# Sensors.net
KiCad netlist of a schematic drawn in Altium Designer
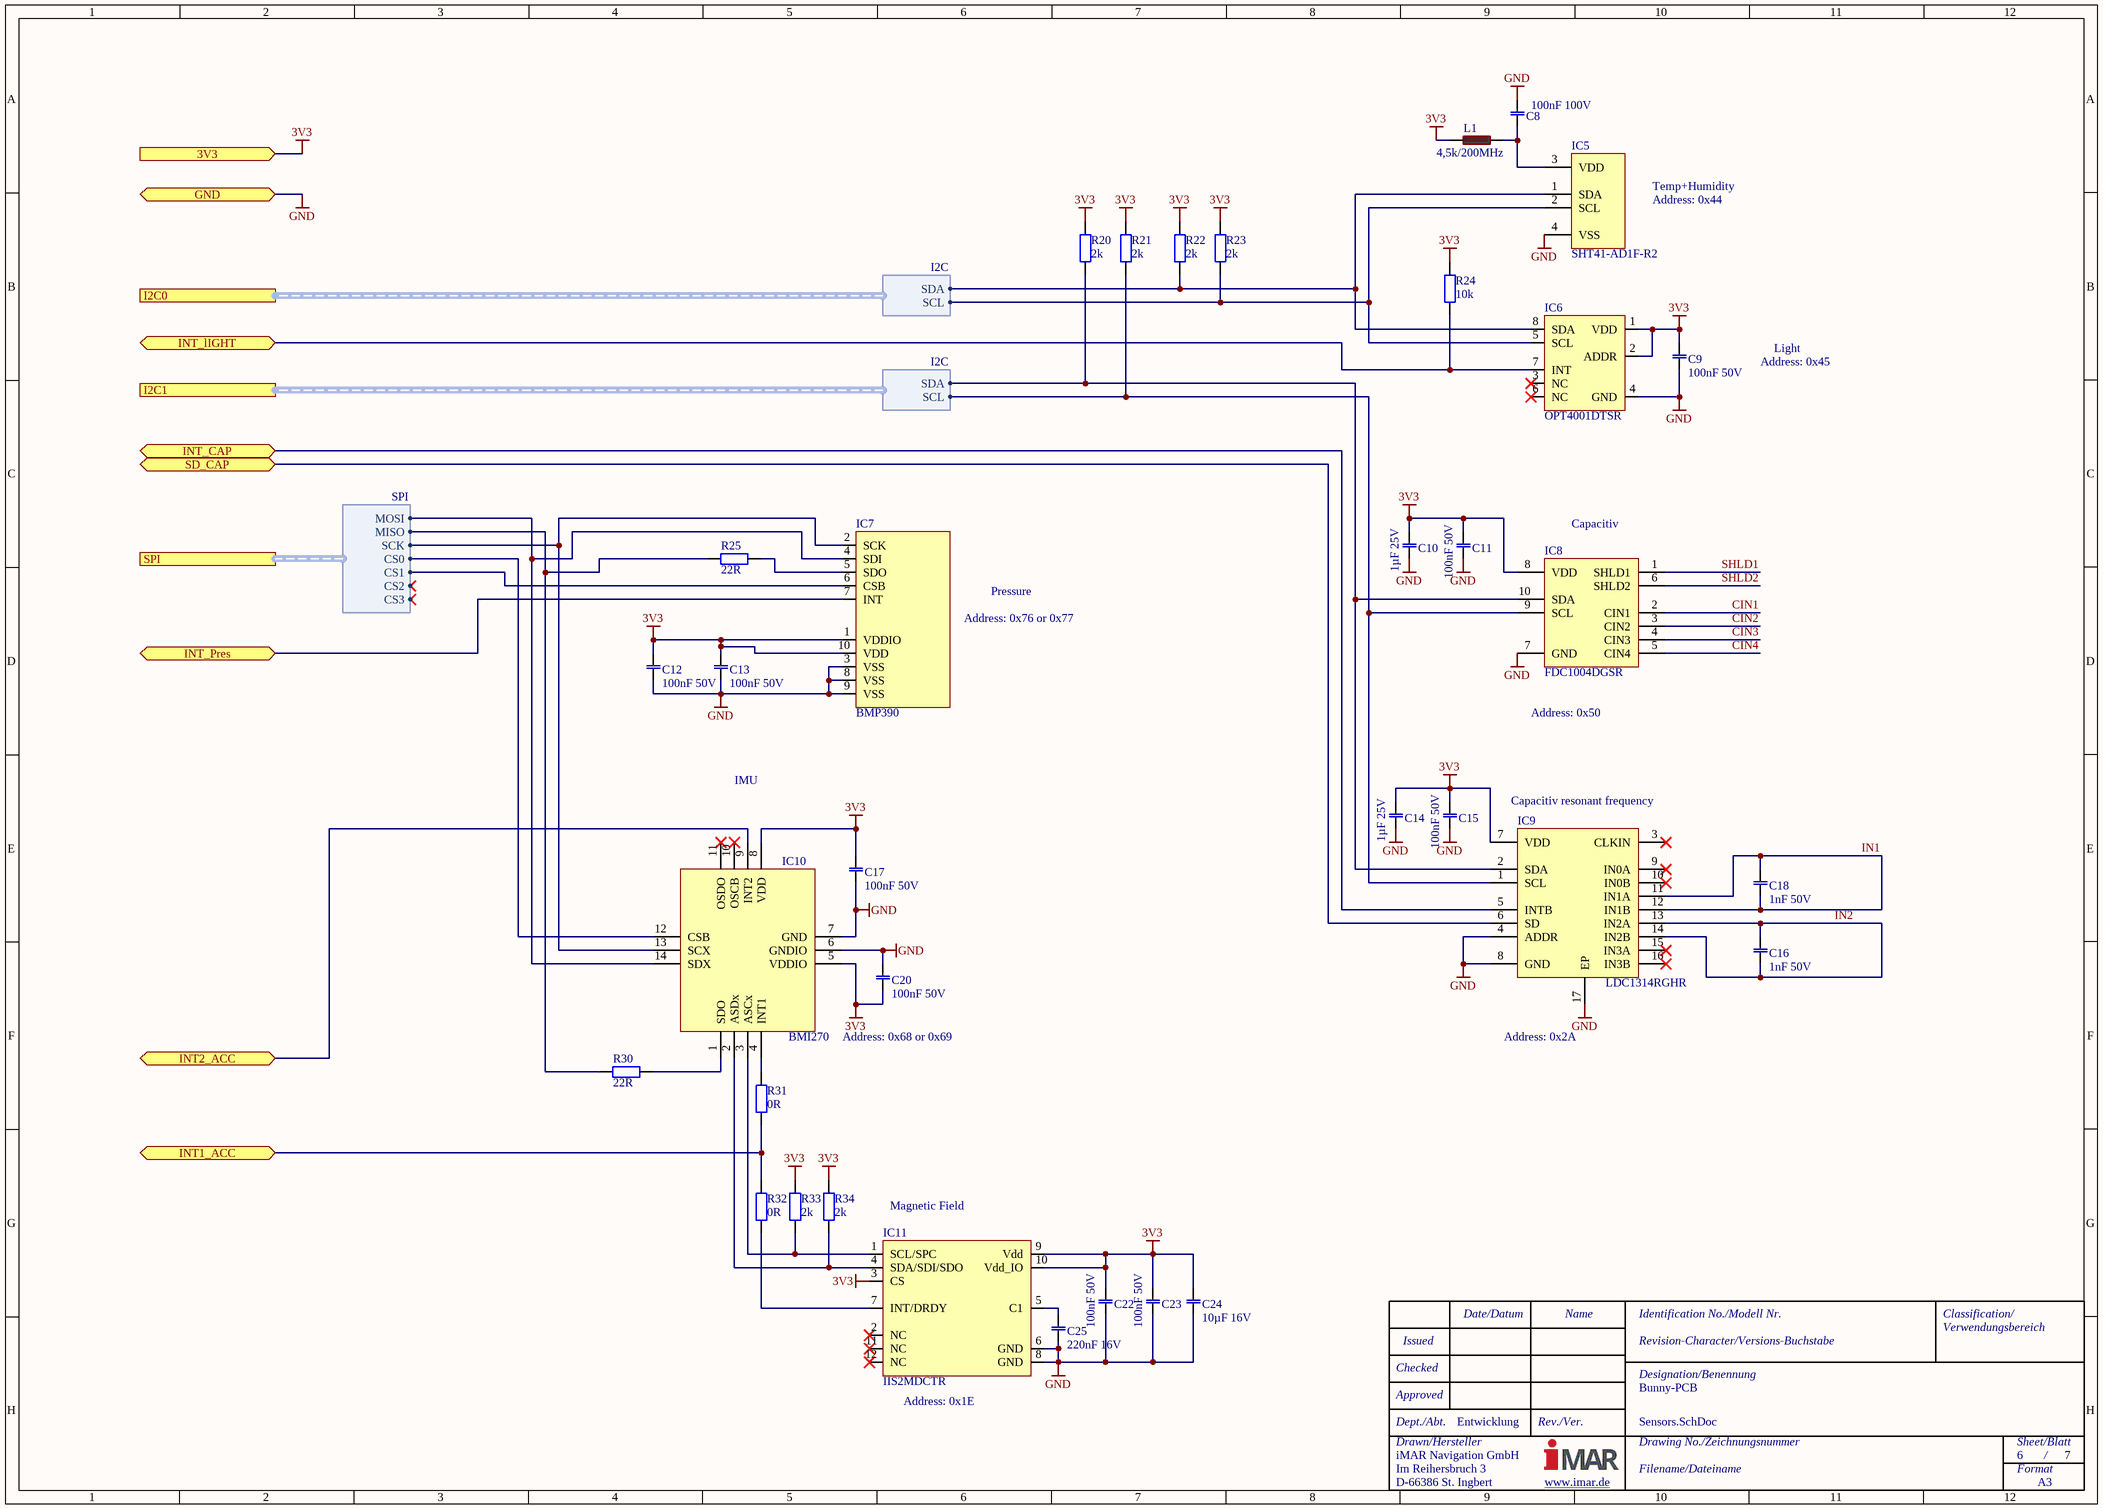
[diagram p0: Sensors.SchDoc]

(export (version "E")
  (design (tool "Eeschema 10.0.6"))
  (components
    (comp (ref "C8")
      (value "100nF 100V")
      (footprint "CAPC1608L")
      (description "100nF  100V  Ceramic  0603  10%  X7R")
      (fields (field (name "VOLTAGE") "100V") (field (name "MANUFACTURER") "unspecified"))
      (libsource (lib "iMAR Workspace") (part "Kondensator"))
    )
    (comp (ref "C9")
      (value "100nF 50V")
      (footprint "CAPC1005N")
      (description "100nF  50V  Ceramic  0402  10%  X7R")
      (fields (field (name "VOLTAGE") "50V") (field (name "MANUFACTURER") "unspecified"))
      (libsource (lib "iMAR Workspace") (part "Kondensator"))
    )
    (comp (ref "C10")
      (value "1µF 25V")
      (footprint "CAPC1005N")
      (description "1µF  25V  Ceramic  0402  10%  X5R")
      (fields (field (name "VOLTAGE") "25V") (field (name "MANUFACTURER") "unspecified"))
      (libsource (lib "iMAR Workspace") (part "Kondensator"))
    )
    (comp (ref "C11")
      (value "100nF 50V")
      (footprint "CAPC1005N")
      (description "100nF  50V  Ceramic  0402  10%  X7R")
      (fields (field (name "VOLTAGE") "50V") (field (name "MANUFACTURER") "unspecified"))
      (libsource (lib "iMAR Workspace") (part "Kondensator"))
    )
    (comp (ref "C12")
      (value "100nF 50V")
      (footprint "CAPC1005N")
      (description "100nF  50V  Ceramic  0402  10%  X7R")
      (fields (field (name "VOLTAGE") "50V") (field (name "MANUFACTURER") "unspecified"))
      (libsource (lib "iMAR Workspace") (part "Kondensator"))
    )
    (comp (ref "C13")
      (value "100nF 50V")
      (footprint "CAPC1005N")
      (description "100nF  50V  Ceramic  0402  10%  X7R")
      (fields (field (name "VOLTAGE") "50V") (field (name "MANUFACTURER") "unspecified"))
      (libsource (lib "iMAR Workspace") (part "Kondensator"))
    )
    (comp (ref "C14")
      (value "1µF 25V")
      (footprint "CAPC1005N")
      (description "1µF  25V  Ceramic  0402  10%  X5R")
      (fields (field (name "VOLTAGE") "25V") (field (name "MANUFACTURER") "unspecified"))
      (libsource (lib "iMAR Workspace") (part "Kondensator"))
    )
    (comp (ref "C15")
      (value "100nF 50V")
      (footprint "CAPC1005N")
      (description "100nF  50V  Ceramic  0402  10%  X7R")
      (fields (field (name "VOLTAGE") "50V") (field (name "MANUFACTURER") "unspecified"))
      (libsource (lib "iMAR Workspace") (part "Kondensator"))
    )
    (comp (ref "C16")
      (value "1nF 50V")
      (footprint "CAPC1608L")
      (description "1nF 50V Ceramic 0603 1% C0G(NP0)")
      (fields (field (name "TOLERANCE") "1%") (field (name "MANUFACTURER") "VISHAY"))
      (libsource (lib "iMAR Workspace") (part "Kondensator"))
    )
    (comp (ref "C17")
      (value "100nF 50V")
      (footprint "CAPC1005N")
      (description "100nF  50V  Ceramic  0402  10%  X7R")
      (fields (field (name "VOLTAGE") "50V") (field (name "MANUFACTURER") "unspecified"))
      (libsource (lib "iMAR Workspace") (part "Kondensator"))
    )
    (comp (ref "C18")
      (value "1nF 50V")
      (footprint "CAPC1608L")
      (description "1nF 50V Ceramic 0603 1% C0G(NP0)")
      (fields (field (name "TOLERANCE") "1%") (field (name "MANUFACTURER") "VISHAY"))
      (libsource (lib "iMAR Workspace") (part "Kondensator"))
    )
    (comp (ref "C20")
      (value "100nF 50V")
      (footprint "CAPC1005N")
      (description "100nF  50V  Ceramic  0402  10%  X7R")
      (fields (field (name "VOLTAGE") "50V") (field (name "MANUFACTURER") "unspecified"))
      (libsource (lib "iMAR Workspace") (part "Kondensator"))
    )
    (comp (ref "C22")
      (value "100nF 50V")
      (footprint "CAPC1005N")
      (description "100nF  50V  Ceramic  0402  10%  X7R")
      (fields (field (name "VOLTAGE") "50V") (field (name "MANUFACTURER") "unspecified"))
      (libsource (lib "iMAR Workspace") (part "Kondensator"))
    )
    (comp (ref "C23")
      (value "100nF 50V")
      (footprint "CAPC1005N")
      (description "100nF  50V  Ceramic  0402  10%  X7R")
      (fields (field (name "VOLTAGE") "50V") (field (name "MANUFACTURER") "unspecified"))
      (libsource (lib "iMAR Workspace") (part "Kondensator"))
    )
    (comp (ref "C24")
      (value "10µF 16V")
      (footprint "CAPC1608L")
      (description "10µF  16V  Ceramic  0603  10%  X5R")
      (fields (field (name "TOLERANCE") "10%") (field (name "MANUFACTURER") "unspecified"))
      (libsource (lib "iMAR Workspace") (part "Kondensator"))
    )
    (comp (ref "C25")
      (value "220nF 16V")
      (footprint "CAPC1005N")
      (description "220nF  16V  Ceramic  0402  10%  X7R")
      (fields (field (name "MANUFACTURER") "unspecified") (field (name "VOLTAGE") "16V"))
      (libsource (lib "iMAR Workspace") (part "Kondensator"))
    )
    (comp (ref "IC5")
      (value "SHT41-AD1F-R2")
      (footprint "SENSIRION_SHT4x")
      (description "Digital humidity and temperature sensor, ±1.8% / max. ±3.5% RH")
      (fields (field (name "MANUFACTURER") "SENSIRION"))
      (libsource (lib "iMAR Workspace") (part "SHT4x"))
    )
    (comp (ref "IC6")
      (value "OPT4001DTSR")
      (footprint "SOT50P160X60-8N")
      (description "High-speed high-precision digital ambient light sensor (ALS)")
      (fields (field (name "MANUFACTURER") "TEXAS INSTRUMENTS"))
      (libsource (lib "iMAR Workspace") (part "OPT4001DTSR"))
    )
    (comp (ref "IC7")
      (value "BMP390")
      (footprint "BMP390")
      (description "Pressure Sensor")
      (fields (field (name "MANUFACTURER") "BOSCH"))
      (libsource (lib "iMAR Workspace") (part "BMP390"))
    )
    (comp (ref "IC8")
      (value "FDC1004DGSR")
      (footprint "TSSOP50P490X110-10N")
      (description "4-Channel Capacitance-to-Digital Converter for Capacitive Sensing Applications")
      (fields (field (name "MANUFACTURER") "TEXAS INSTRUMENTS"))
      (libsource (lib "iMAR Workspace") (part "FDC1004"))
    )
    (comp (ref "IC9")
      (value "LDC1314RGHR")
      (footprint "QFN65P400X400X80_HS-17N")
      (description "Data Acquisition ADCs/DACs - Specialised 12-bit Inductance- t o-Digital Converter")
      (fields (field (name "MANUFACTURER") "TEXAS INSTRUMENTS"))
      (libsource (lib "iMAR Workspace") (part "LDC1314"))
    )
    (comp (ref "IC10")
      (value "BMI270")
      (footprint "BOSCH_LGA14_BMI_vergroesserte_Pads")
      (description "6-axis, smart, low-power Inertial Measurement Unit")
      (fields (field (name "MANUFACTURER") "BOSCH"))
      (libsource (lib "iMAR Workspace") (part "BMI270"))
    )
    (comp (ref "IC11")
      (value "IIS2MDCTR")
      (footprint "ST_IIS2MDCTR_LGA12C50P4X4_200X200X70")
      (description "High accuracy, ultra-low-power ,3-axis digital output magnetometer")
      (fields (field (name "MANUFACTURER") "ST Microelectronics"))
      (libsource (lib "iMAR Workspace") (part "IIS2MDCTR"))
    )
    (comp (ref "L1")
      (value "4,5k/200MHz")
      (footprint "IND_WE_CBF_0603_Wide_Band")
      (description "4,5k/200MHz  500mA  0603  WE-CBF SMD EMI Suppression Ferrite Bead")
      (fields (field (name "MANUFACTURER") "WUERTH ELEKTRONIK"))
      (libsource (lib "iMAR Workspace") (part "Ferrit-Perle"))
    )
    (comp (ref "R20")
      (value "2k")
      (footprint "RESC1005L")
      (description "2k  0402  62mW  1%  100ppm  50V")
      (fields (field (name "POWER") "62mW") (field (name "TOLERANCE") "1%"))
      (libsource (lib "iMAR Workspace") (part "Widerstand"))
    )
    (comp (ref "R21")
      (value "2k")
      (footprint "RESC1005L")
      (description "2k  0402  62mW  1%  100ppm  50V")
      (fields (field (name "POWER") "62mW") (field (name "TOLERANCE") "1%"))
      (libsource (lib "iMAR Workspace") (part "Widerstand"))
    )
    (comp (ref "R22")
      (value "2k")
      (footprint "RESC1005L")
      (description "2k  0402  62mW  1%  100ppm  50V")
      (fields (field (name "POWER") "62mW") (field (name "TOLERANCE") "1%"))
      (libsource (lib "iMAR Workspace") (part "Widerstand"))
    )
    (comp (ref "R23")
      (value "2k")
      (footprint "RESC1005L")
      (description "2k  0402  62mW  1%  100ppm  50V")
      (fields (field (name "POWER") "62mW") (field (name "TOLERANCE") "1%"))
      (libsource (lib "iMAR Workspace") (part "Widerstand"))
    )
    (comp (ref "R24")
      (value "10k")
      (footprint "RESC1005L")
      (description "10k  0402  62mW  1%  100ppm  50V")
      (fields (field (name "MANUFACTURER") "unspecified") (field (name "POWER") "62mW"))
      (libsource (lib "iMAR Workspace") (part "Widerstand"))
    )
    (comp (ref "R25")
      (value "22R")
      (footprint "RESC1005L")
      (description "22R  0402  62mW  1%  100ppm  50V")
      (fields (field (name "MANUFACTURER") "unspecified") (field (name "POWER") "62mW"))
      (libsource (lib "") (part "Widerstand_1"))
    )
    (comp (ref "R30")
      (value "22R")
      (footprint "RESC1005L")
      (description "22R  0402  62mW  1%  100ppm  50V")
      (fields (field (name "MANUFACTURER") "unspecified") (field (name "POWER") "62mW"))
      (libsource (lib "") (part "Widerstand_1"))
    )
    (comp (ref "R31")
      (value "0R")
      (footprint "RESC1005L")
      (description "0R  0402  0mW  0%  0ppm  0V")
      (fields (field (name "VOLTAGE") "0V") (field (name "TOLERANCE") "0%"))
      (libsource (lib "iMAR Workspace") (part "Widerstand"))
    )
    (comp (ref "R32")
      (value "0R")
      (footprint "RESC1005L")
      (description "0R  0402  0mW  0%  0ppm  0V")
      (fields (field (name "VOLTAGE") "0V") (field (name "TOLERANCE") "0%"))
      (libsource (lib "iMAR Workspace") (part "Widerstand"))
    )
    (comp (ref "R33")
      (value "2k")
      (footprint "RESC1005L")
      (description "2k  0402  62mW  1%  100ppm  50V")
      (fields (field (name "POWER") "62mW") (field (name "TOLERANCE") "1%"))
      (libsource (lib "iMAR Workspace") (part "Widerstand"))
    )
    (comp (ref "R34")
      (value "2k")
      (footprint "RESC1005L")
      (description "2k  0402  62mW  1%  100ppm  50V")
      (fields (field (name "POWER") "62mW") (field (name "TOLERANCE") "1%"))
      (libsource (lib "iMAR Workspace") (part "Widerstand"))
    )
  )
  (nets
    (net (code "3") (name "/CIN1") (class "Default")
      (node (ref "IC8") (pin "2") (pinfunction "CIN1_2") (pintype "passive"))
    )
    (net (code "4") (name "/CIN2") (class "Default")
      (node (ref "IC8") (pin "3") (pinfunction "CIN2_3") (pintype "passive"))
    )
    (net (code "5") (name "/CIN3") (class "Default")
      (node (ref "IC8") (pin "4") (pinfunction "CIN3_4") (pintype "passive"))
    )
    (net (code "6") (name "/CIN4") (class "Default")
      (node (ref "IC8") (pin "5") (pinfunction "CIN4_5") (pintype "passive"))
    )
    (net (code "7") (name "/CS0") (class "Default")
      (node (ref "IC10") (pin "12") (pinfunction "CSB_12") (pintype "passive"))
    )
    (net (code "8") (name "/CS1") (class "Default")
      (node (ref "IC7") (pin "6") (pinfunction "CSB_6") (pintype "passive"))
    )
    (net (code "9") (name "/IN1") (class "Default")
      (node (ref "C18") (pin "1") (pinfunction "1_1") (pintype "passive"))
      (node (ref "C18") (pin "2") (pinfunction "2_2") (pintype "passive"))
      (node (ref "IC9") (pin "11") (pinfunction "IN1A_11") (pintype "passive"))
      (node (ref "IC9") (pin "12") (pinfunction "IN1B_12") (pintype "passive"))
    )
    (net (code "10") (name "/IN2") (class "Default")
      (node (ref "C16") (pin "1") (pinfunction "1_1") (pintype "passive"))
      (node (ref "C16") (pin "2") (pinfunction "2_2") (pintype "passive"))
      (node (ref "IC9") (pin "13") (pinfunction "IN2A_13") (pintype "passive"))
      (node (ref "IC9") (pin "14") (pinfunction "IN2B_14") (pintype "passive"))
    )
    (net (code "11") (name "/INT1_ACC") (class "Default")
      (node (ref "R31") (pin "1") (pinfunction "1_1") (pintype "passive"))
      (node (ref "R32") (pin "2") (pinfunction "2_2") (pintype "passive"))
    )
    (net (code "12") (name "/INT2_ACC") (class "Default")
      (node (ref "IC10") (pin "9") (pinfunction "INT2_9") (pintype "passive"))
    )
    (net (code "13") (name "/INT_CAP") (class "Default")
      (node (ref "IC9") (pin "5") (pinfunction "INTB_5") (pintype "passive"))
    )
    (net (code "14") (name "/INT_Pres") (class "Default")
      (node (ref "IC7") (pin "7") (pinfunction "INT_7") (pintype "passive"))
    )
    (net (code "15") (name "/INT_lIGHT") (class "Default")
      (node (ref "IC6") (pin "7") (pinfunction "INT_7") (pintype "passive"))
      (node (ref "R24") (pin "1") (pinfunction "1_1") (pintype "passive"))
    )
    (net (code "16") (name "/MISO") (class "Default")
      (node (ref "R25") (pin "1") (pinfunction "1_1") (pintype "passive"))
      (node (ref "R30") (pin "1") (pinfunction "1_1") (pintype "passive"))
    )
    (net (code "17") (name "/MOSI") (class "Default")
      (node (ref "IC10") (pin "14") (pinfunction "SDX_14") (pintype "passive"))
      (node (ref "IC7") (pin "4") (pinfunction "SDI_4") (pintype "passive"))
    )
    (net (code "18") (name "/SCK") (class "Default")
      (node (ref "IC10") (pin "13") (pinfunction "SCX_13") (pintype "passive"))
      (node (ref "IC7") (pin "2") (pinfunction "SCK_2") (pintype "passive"))
    )
    (net (code "19") (name "/SD_CAP") (class "Default")
      (node (ref "IC9") (pin "6") (pinfunction "SD_6") (pintype "passive"))
    )
    (net (code "20") (name "/SHLD1") (class "Default")
      (node (ref "IC8") (pin "1") (pinfunction "SHLD1_1") (pintype "passive"))
    )
    (net (code "21") (name "/SHLD2") (class "Default")
      (node (ref "IC8") (pin "6") (pinfunction "SHLD2_6") (pintype "passive"))
    )
    (net (code "24") (name "3V3") (class "Default")
      (node (ref "C10") (pin "2") (pinfunction "2_2") (pintype "passive"))
      (node (ref "C11") (pin "2") (pinfunction "2_2") (pintype "passive"))
      (node (ref "C12") (pin "2") (pinfunction "2_2") (pintype "passive"))
      (node (ref "C13") (pin "2") (pinfunction "2_2") (pintype "passive"))
      (node (ref "C14") (pin "2") (pinfunction "2_2") (pintype "passive"))
      (node (ref "C15") (pin "2") (pinfunction "2_2") (pintype "passive"))
      (node (ref "C17") (pin "2") (pinfunction "2_2") (pintype "passive"))
      (node (ref "C20") (pin "1") (pinfunction "1_1") (pintype "passive"))
      (node (ref "C22") (pin "2") (pinfunction "2_2") (pintype "passive"))
      (node (ref "C23") (pin "2") (pinfunction "2_2") (pintype "passive"))
      (node (ref "C24") (pin "2") (pinfunction "2_2") (pintype "passive"))
      (node (ref "C9") (pin "2") (pinfunction "2_2") (pintype "passive"))
      (node (ref "IC10") (pin "5") (pinfunction "VDDIO_5") (pintype "passive"))
      (node (ref "IC10") (pin "8") (pinfunction "VDD_8") (pintype "passive"))
      (node (ref "IC11") (pin "10") (pinfunction "Vdd_IO_10") (pintype "passive"))
      (node (ref "IC11") (pin "3") (pinfunction "CS_3") (pintype "passive"))
      (node (ref "IC11") (pin "9") (pinfunction "Vdd_9") (pintype "passive"))
      (node (ref "IC6") (pin "1") (pinfunction "VDD_1") (pintype "passive"))
      (node (ref "IC6") (pin "2") (pinfunction "ADDR_2") (pintype "passive"))
      (node (ref "IC7") (pin "1") (pinfunction "VDDIO_1") (pintype "passive"))
      (node (ref "IC7") (pin "10") (pinfunction "VDD_10") (pintype "passive"))
      (node (ref "IC8") (pin "8") (pinfunction "VDD_8") (pintype "passive"))
      (node (ref "IC9") (pin "7") (pinfunction "VDD_7") (pintype "passive"))
      (node (ref "L1") (pin "1") (pinfunction "1_1") (pintype "passive"))
      (node (ref "R20") (pin "2") (pinfunction "2_2") (pintype "passive"))
      (node (ref "R21") (pin "2") (pinfunction "2_2") (pintype "passive"))
      (node (ref "R22") (pin "2") (pinfunction "2_2") (pintype "passive"))
      (node (ref "R23") (pin "2") (pinfunction "2_2") (pintype "passive"))
      (node (ref "R24") (pin "2") (pinfunction "2_2") (pintype "passive"))
      (node (ref "R33") (pin "2") (pinfunction "2_2") (pintype "passive"))
      (node (ref "R34") (pin "2") (pinfunction "2_2") (pintype "passive"))
    )
    (net (code "25") (name "GND") (class "Default")
      (node (ref "C10") (pin "1") (pinfunction "1_1") (pintype "passive"))
      (node (ref "C11") (pin "1") (pinfunction "1_1") (pintype "passive"))
      (node (ref "C12") (pin "1") (pinfunction "1_1") (pintype "passive"))
      (node (ref "C13") (pin "1") (pinfunction "1_1") (pintype "passive"))
      (node (ref "C14") (pin "1") (pinfunction "1_1") (pintype "passive"))
      (node (ref "C15") (pin "1") (pinfunction "1_1") (pintype "passive"))
      (node (ref "C17") (pin "1") (pinfunction "1_1") (pintype "passive"))
      (node (ref "C20") (pin "2") (pinfunction "2_2") (pintype "passive"))
      (node (ref "C22") (pin "1") (pinfunction "1_1") (pintype "passive"))
      (node (ref "C23") (pin "1") (pinfunction "1_1") (pintype "passive"))
      (node (ref "C24") (pin "1") (pinfunction "1_1") (pintype "passive"))
      (node (ref "C25") (pin "2") (pinfunction "2_2") (pintype "passive"))
      (node (ref "C8") (pin "1") (pinfunction "1_1") (pintype "passive"))
      (node (ref "C9") (pin "1") (pinfunction "1_1") (pintype "passive"))
      (node (ref "IC10") (pin "6") (pinfunction "GNDIO_6") (pintype "passive"))
      (node (ref "IC10") (pin "7") (pinfunction "GND_7") (pintype "passive"))
      (node (ref "IC11") (pin "6") (pinfunction "GND_6") (pintype "passive"))
      (node (ref "IC11") (pin "8") (pinfunction "GND_8") (pintype "passive"))
      (node (ref "IC5") (pin "4") (pinfunction "VSS_4") (pintype "passive"))
      (node (ref "IC6") (pin "4") (pinfunction "GND_4") (pintype "passive"))
      (node (ref "IC7") (pin "3") (pinfunction "VSS_3") (pintype "passive"))
      (node (ref "IC7") (pin "8") (pinfunction "VSS_8") (pintype "passive"))
      (node (ref "IC7") (pin "9") (pinfunction "VSS_9") (pintype "passive"))
      (node (ref "IC8") (pin "7") (pinfunction "GND_7") (pintype "passive"))
      (node (ref "IC9") (pin "17") (pinfunction "EP_17") (pintype "passive"))
      (node (ref "IC9") (pin "4") (pinfunction "ADDR_4") (pintype "passive"))
      (node (ref "IC9") (pin "8") (pinfunction "GND_8") (pintype "passive"))
    )
    (net (code "26") (name "Net-(IC5-SCL)") (class "Default")
      (node (ref "IC5") (pin "2") (pinfunction "SCL_2") (pintype "passive"))
      (node (ref "IC6") (pin "5") (pinfunction "SCL_5") (pintype "passive"))
      (node (ref "R23") (pin "1") (pinfunction "1_1") (pintype "passive"))
    )
    (net (code "27") (name "Net-(IC5-SDA)") (class "Default")
      (node (ref "IC5") (pin "1") (pinfunction "SDA_1") (pintype "passive"))
      (node (ref "IC6") (pin "8") (pinfunction "SDA_8") (pintype "passive"))
      (node (ref "R22") (pin "1") (pinfunction "1_1") (pintype "passive"))
    )
    (net (code "28") (name "Net-(IC5-VDD)") (class "Default")
      (node (ref "C8") (pin "2") (pinfunction "2_2") (pintype "passive"))
      (node (ref "IC5") (pin "3") (pinfunction "VDD_3") (pintype "passive"))
      (node (ref "L1") (pin "2") (pinfunction "2_2") (pintype "passive"))
    )
    (net (code "29") (name "Net-(IC7-SDO)") (class "Default")
      (node (ref "IC7") (pin "5") (pinfunction "SDO_5") (pintype "passive"))
      (node (ref "R25") (pin "2") (pinfunction "2_2") (pintype "passive"))
    )
    (net (code "30") (name "Net-(IC8-SCL)") (class "Default")
      (node (ref "IC8") (pin "9") (pinfunction "SCL_9") (pintype "passive"))
      (node (ref "IC9") (pin "1") (pinfunction "SCL_1") (pintype "passive"))
      (node (ref "R21") (pin "1") (pinfunction "1_1") (pintype "passive"))
    )
    (net (code "31") (name "Net-(IC8-SDA)") (class "Default")
      (node (ref "IC8") (pin "10") (pinfunction "SDA_10") (pintype "passive"))
      (node (ref "IC9") (pin "2") (pinfunction "SDA_2") (pintype "passive"))
      (node (ref "R20") (pin "1") (pinfunction "1_1") (pintype "passive"))
    )
    (net (code "32") (name "Net-(IC10-ASCx)") (class "Default")
      (node (ref "IC10") (pin "3") (pinfunction "ASCx_3") (pintype "passive"))
      (node (ref "IC11") (pin "1") (pinfunction "SCL/SPC_1") (pintype "passive"))
      (node (ref "R33") (pin "1") (pinfunction "1_1") (pintype "passive"))
    )
    (net (code "33") (name "Net-(IC10-ASDx)") (class "Default")
      (node (ref "IC10") (pin "2") (pinfunction "ASDx_2") (pintype "passive"))
      (node (ref "IC11") (pin "4") (pinfunction "SDA/SDI/SDO_4") (pintype "passive"))
      (node (ref "R34") (pin "1") (pinfunction "1_1") (pintype "passive"))
    )
    (net (code "34") (name "Net-(IC10-INT1)") (class "Default")
      (node (ref "IC10") (pin "4") (pinfunction "INT1_4") (pintype "passive"))
      (node (ref "R31") (pin "2") (pinfunction "2_2") (pintype "passive"))
    )
    (net (code "35") (name "Net-(IC10-SDO)") (class "Default")
      (node (ref "IC10") (pin "1") (pinfunction "SDO_1") (pintype "passive"))
      (node (ref "R30") (pin "2") (pinfunction "2_2") (pintype "passive"))
    )
    (net (code "36") (name "Net-(IC11-C1)") (class "Default")
      (node (ref "C25") (pin "1") (pinfunction "1_1") (pintype "passive"))
      (node (ref "IC11") (pin "5") (pinfunction "C1_5") (pintype "passive"))
    )
    (net (code "37") (name "Net-(IC11-INT{slash}DRDY)") (class "Default")
      (node (ref "IC11") (pin "7") (pinfunction "INT/DRDY_7") (pintype "passive"))
      (node (ref "R32") (pin "1") (pinfunction "1_1") (pintype "passive"))
    )
    (net (code "38") (name "unconnected-(IC6-NC-Pad3)") (class "Default")
      (node (ref "IC6") (pin "3") (pinfunction "NC_3") (pintype "passive+no_connect"))
    )
    (net (code "39") (name "unconnected-(IC6-NC-Pad6)") (class "Default")
      (node (ref "IC6") (pin "6") (pinfunction "NC_6") (pintype "passive+no_connect"))
    )
    (net (code "40") (name "unconnected-(IC9-CLKIN-Pad3)") (class "Default")
      (node (ref "IC9") (pin "3") (pinfunction "CLKIN_3") (pintype "passive+no_connect"))
    )
    (net (code "41") (name "unconnected-(IC9-IN0A-Pad9)") (class "Default")
      (node (ref "IC9") (pin "9") (pinfunction "IN0A_9") (pintype "passive+no_connect"))
    )
    (net (code "42") (name "unconnected-(IC9-IN0B-Pad10)") (class "Default")
      (node (ref "IC9") (pin "10") (pinfunction "IN0B_10") (pintype "passive+no_connect"))
    )
    (net (code "43") (name "unconnected-(IC9-IN3A-Pad15)") (class "Default")
      (node (ref "IC9") (pin "15") (pinfunction "IN3A_15") (pintype "passive+no_connect"))
    )
    (net (code "44") (name "unconnected-(IC9-IN3B-Pad16)") (class "Default")
      (node (ref "IC9") (pin "16") (pinfunction "IN3B_16") (pintype "passive+no_connect"))
    )
    (net (code "45") (name "unconnected-(IC10-OSCB-Pad10)") (class "Default")
      (node (ref "IC10") (pin "10") (pinfunction "OSCB_10") (pintype "passive+no_connect"))
    )
    (net (code "46") (name "unconnected-(IC10-OSDO-Pad11)") (class "Default")
      (node (ref "IC10") (pin "11") (pinfunction "OSDO_11") (pintype "passive+no_connect"))
    )
    (net (code "47") (name "unconnected-(IC11-NC-Pad2)") (class "Default")
      (node (ref "IC11") (pin "2") (pinfunction "NC_2") (pintype "passive+no_connect"))
    )
    (net (code "48") (name "unconnected-(IC11-NC-Pad11)") (class "Default")
      (node (ref "IC11") (pin "11") (pinfunction "NC_11") (pintype "passive+no_connect"))
    )
    (net (code "49") (name "unconnected-(IC11-NC-Pad12)") (class "Default")
      (node (ref "IC11") (pin "12") (pinfunction "NC_12") (pintype "passive+no_connect"))
    )
  )
)
